# Connectors.net
KiCad netlist of a schematic drawn in Altium Designer
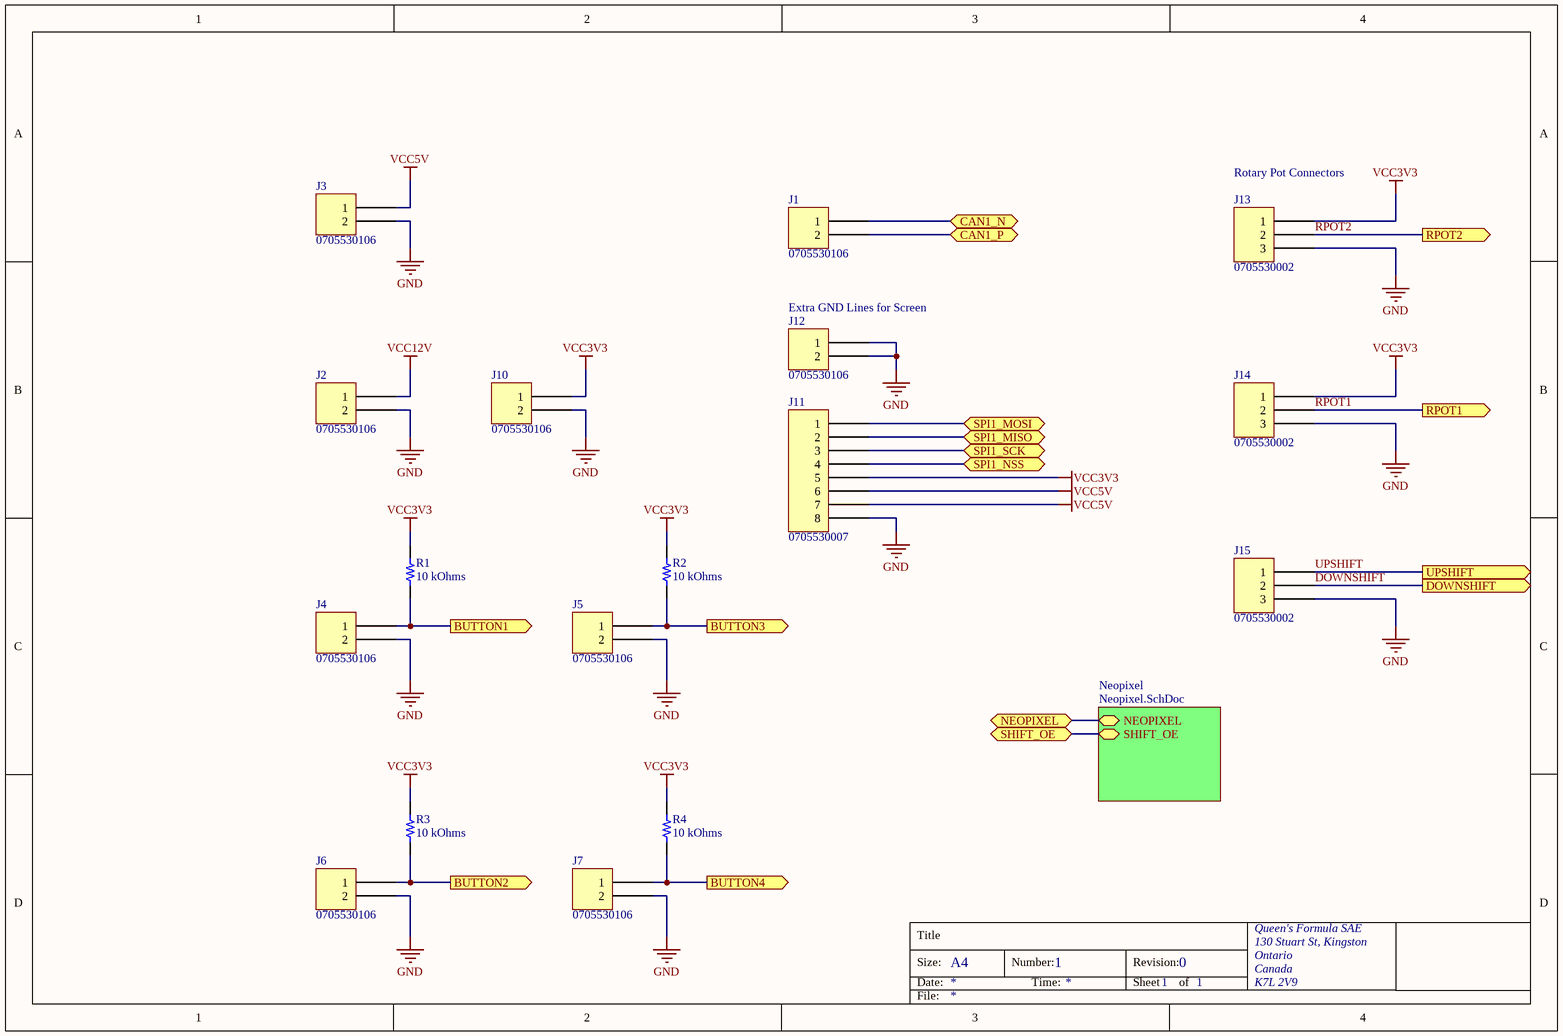
[diagram p0: Connectors.SchDoc]

(export (version "E")
  (design (tool "Eeschema 10.0.6"))
  (components
    (comp (ref "J1")
      (value "0705530106")
      (footprint "MOLEX SDA-70553-2PIN")
      (description "CONN HEADER R/A 2POS 2.54MM")
      (fields (field (name "MANUFACTURER") "Molex"))
      (libsource (lib "Celestial") (part "2 Pin"))
    )
    (comp (ref "J2")
      (value "0705530106")
      (footprint "MOLEX SDA-70553-2PIN")
      (description "CONN HEADER R/A 2POS 2.54MM")
      (fields (field (name "MANUFACTURER") "Molex"))
      (libsource (lib "Celestial") (part "2 Pin"))
    )
    (comp (ref "J3")
      (value "0705530106")
      (footprint "MOLEX SDA-70553-2PIN")
      (description "CONN HEADER R/A 2POS 2.54MM")
      (fields (field (name "MANUFACTURER") "Molex"))
      (libsource (lib "Celestial") (part "2 Pin"))
    )
    (comp (ref "J4")
      (value "0705530106")
      (footprint "MOLEX SDA-70553-2PIN")
      (description "CONN HEADER R/A 2POS 2.54MM")
      (fields (field (name "MANUFACTURER") "Molex"))
      (libsource (lib "Celestial") (part "2 Pin"))
    )
    (comp (ref "J5")
      (value "0705530106")
      (footprint "MOLEX SDA-70553-2PIN")
      (description "CONN HEADER R/A 2POS 2.54MM")
      (fields (field (name "MANUFACTURER") "Molex"))
      (libsource (lib "Celestial") (part "2 Pin"))
    )
    (comp (ref "J6")
      (value "0705530106")
      (footprint "MOLEX SDA-70553-2PIN")
      (description "CONN HEADER R/A 2POS 2.54MM")
      (fields (field (name "MANUFACTURER") "Molex"))
      (libsource (lib "Celestial") (part "2 Pin"))
    )
    (comp (ref "J7")
      (value "0705530106")
      (footprint "MOLEX SDA-70553-2PIN")
      (description "CONN HEADER R/A 2POS 2.54MM")
      (fields (field (name "MANUFACTURER") "Molex"))
      (libsource (lib "Celestial") (part "2 Pin"))
    )
    (comp (ref "J10")
      (value "0705530106")
      (footprint "MOLEX SDA-70553-2PIN")
      (description "CONN HEADER R/A 2POS 2.54MM")
      (fields (field (name "MANUFACTURER") "Molex"))
      (libsource (lib "Celestial") (part "2 Pin"))
    )
    (comp (ref "J11")
      (value "0705530007")
      (footprint "MOLEX SDA-70553-8PIN")
      (description "CONN HEADER R/A 8POS 2.54MM")
      (libsource (lib "CAL") (part "8 Pin"))
    )
    (comp (ref "J12")
      (value "0705530106")
      (footprint "MOLEX SDA-70553-2PIN")
      (description "CONN HEADER R/A 2POS 2.54MM")
      (fields (field (name "MANUFACTURER") "Molex"))
      (libsource (lib "Celestial") (part "2 Pin"))
    )
    (comp (ref "J13")
      (value "0705530002")
      (footprint "MOLEX SDA-70553-3PIN")
      (description "CONN HEADER R/A 3POS 2.54MM")
      (libsource (lib "Celestial") (part "3 Pin"))
    )
    (comp (ref "J14")
      (value "0705530002")
      (footprint "MOLEX SDA-70553-3PIN")
      (description "CONN HEADER R/A 3POS 2.54MM")
      (fields (field (name "MANUFACTURER") "Molex"))
      (libsource (lib "Celestial") (part "3 Pin"))
    )
    (comp (ref "J15")
      (value "0705530002")
      (footprint "MOLEX SDA-70553-3PIN")
      (description "CONN HEADER R/A 3POS 2.54MM")
      (fields (field (name "MANUFACTURER") "Molex"))
      (libsource (lib "CAL") (part "3 Pin"))
    )
    (comp (ref "R1")
      (value "10 kOhms")
      (footprint "RES 0402_1005")
      (description "RES SMD 10K OHM 0.1% 1/16W 0402")
      (fields
        (field (name "PART NUMBER") "CPF0402B10KE1")
        (field (name "MANUFACTURER") "TE Connectivity Passive Product")
      )
      (libsource (lib "Celestial") (part "Resistor"))
    )
    (comp (ref "R2")
      (value "10 kOhms")
      (footprint "RES 0402_1005")
      (description "RES SMD 10K OHM 0.1% 1/16W 0402")
      (fields
        (field (name "PART NUMBER") "CPF0402B10KE1")
        (field (name "MANUFACTURER") "TE Connectivity Passive Product")
      )
      (libsource (lib "Celestial") (part "Resistor"))
    )
    (comp (ref "R3")
      (value "10 kOhms")
      (footprint "RES 0402_1005")
      (description "RES SMD 10K OHM 0.1% 1/16W 0402")
      (fields
        (field (name "PART NUMBER") "CPF0402B10KE1")
        (field (name "MANUFACTURER") "TE Connectivity Passive Product")
      )
      (libsource (lib "Celestial") (part "Resistor"))
    )
    (comp (ref "R4")
      (value "10 kOhms")
      (footprint "RES 0402_1005")
      (description "RES SMD 10K OHM 0.1% 1/16W 0402")
      (fields
        (field (name "PART NUMBER") "CPF0402B10KE1")
        (field (name "MANUFACTURER") "TE Connectivity Passive Product")
      )
      (libsource (lib "Celestial") (part "Resistor"))
    )
  )
  (nets
    (net (code "1") (name "/BUTTON1") (class "Default")
      (node (ref "J4") (pin "1") (pinfunction "1_1") (pintype "passive"))
      (node (ref "R1") (pin "1") (pinfunction "1_1") (pintype "passive"))
    )
    (net (code "2") (name "/BUTTON2") (class "Default")
      (node (ref "J6") (pin "1") (pinfunction "1_1") (pintype "passive"))
      (node (ref "R3") (pin "1") (pinfunction "1_1") (pintype "passive"))
    )
    (net (code "3") (name "/BUTTON3") (class "Default")
      (node (ref "J5") (pin "1") (pinfunction "1_1") (pintype "passive"))
      (node (ref "R2") (pin "1") (pinfunction "1_1") (pintype "passive"))
    )
    (net (code "4") (name "/BUTTON4") (class "Default")
      (node (ref "J7") (pin "1") (pinfunction "1_1") (pintype "passive"))
      (node (ref "R4") (pin "1") (pinfunction "1_1") (pintype "passive"))
    )
    (net (code "5") (name "/CAN1_N") (class "Default")
      (node (ref "J1") (pin "1") (pinfunction "1_1") (pintype "passive"))
    )
    (net (code "6") (name "/CAN1_P") (class "Default")
      (node (ref "J1") (pin "2") (pinfunction "2_2") (pintype "passive"))
    )
    (net (code "7") (name "/DOWNSHIFT") (class "Default")
      (node (ref "J15") (pin "2") (pinfunction "2_2") (pintype "passive"))
    )
    (net (code "9") (name "/RPOT1") (class "Default")
      (node (ref "J14") (pin "2") (pinfunction "2_2") (pintype "passive"))
    )
    (net (code "10") (name "/RPOT2") (class "Default")
      (node (ref "J13") (pin "2") (pinfunction "2_2") (pintype "passive"))
    )
    (net (code "12") (name "/SPI1_MISO") (class "Default")
      (node (ref "J11") (pin "2") (pinfunction "2_2") (pintype "passive"))
    )
    (net (code "13") (name "/SPI1_MOSI") (class "Default")
      (node (ref "J11") (pin "1") (pinfunction "1_1") (pintype "passive"))
    )
    (net (code "14") (name "/SPI1_NSS") (class "Default")
      (node (ref "J11") (pin "4") (pinfunction "4_4") (pintype "passive"))
    )
    (net (code "15") (name "/SPI1_SCK") (class "Default")
      (node (ref "J11") (pin "3") (pinfunction "3_3") (pintype "passive"))
    )
    (net (code "16") (name "/UPSHIFT") (class "Default")
      (node (ref "J15") (pin "1") (pinfunction "1_1") (pintype "passive"))
    )
    (net (code "17") (name "GND") (class "Default")
      (node (ref "J10") (pin "2") (pinfunction "2_2") (pintype "passive"))
      (node (ref "J11") (pin "8") (pinfunction "8_8") (pintype "passive"))
      (node (ref "J12") (pin "1") (pinfunction "1_1") (pintype "passive"))
      (node (ref "J12") (pin "2") (pinfunction "2_2") (pintype "passive"))
      (node (ref "J13") (pin "3") (pinfunction "3_3") (pintype "passive"))
      (node (ref "J14") (pin "3") (pinfunction "3_3") (pintype "passive"))
      (node (ref "J15") (pin "3") (pinfunction "3_3") (pintype "passive"))
      (node (ref "J2") (pin "2") (pinfunction "2_2") (pintype "passive"))
      (node (ref "J3") (pin "2") (pinfunction "2_2") (pintype "passive"))
      (node (ref "J4") (pin "2") (pinfunction "2_2") (pintype "passive"))
      (node (ref "J5") (pin "2") (pinfunction "2_2") (pintype "passive"))
      (node (ref "J6") (pin "2") (pinfunction "2_2") (pintype "passive"))
      (node (ref "J7") (pin "2") (pinfunction "2_2") (pintype "passive"))
    )
    (net (code "18") (name "VCC3V3") (class "Default")
      (node (ref "J10") (pin "1") (pinfunction "1_1") (pintype "passive"))
      (node (ref "J11") (pin "5") (pinfunction "5_5") (pintype "passive"))
      (node (ref "J13") (pin "1") (pinfunction "1_1") (pintype "passive"))
      (node (ref "J14") (pin "1") (pinfunction "1_1") (pintype "passive"))
      (node (ref "R1") (pin "2") (pinfunction "2_2") (pintype "passive"))
      (node (ref "R2") (pin "2") (pinfunction "2_2") (pintype "passive"))
      (node (ref "R3") (pin "2") (pinfunction "2_2") (pintype "passive"))
      (node (ref "R4") (pin "2") (pinfunction "2_2") (pintype "passive"))
    )
    (net (code "19") (name "VCC5V") (class "Default")
      (node (ref "J11") (pin "6") (pinfunction "6_6") (pintype "passive"))
      (node (ref "J11") (pin "7") (pinfunction "7_7") (pintype "passive"))
      (node (ref "J3") (pin "1") (pinfunction "1_1") (pintype "passive"))
    )
    (net (code "20") (name "VCC12V") (class "Default")
      (node (ref "J2") (pin "1") (pinfunction "1_1") (pintype "passive"))
    )
  )
)
